# hp6060b_v1_8_add_buffer.net
KiCad netlist of a schematic drawn in EAGLE
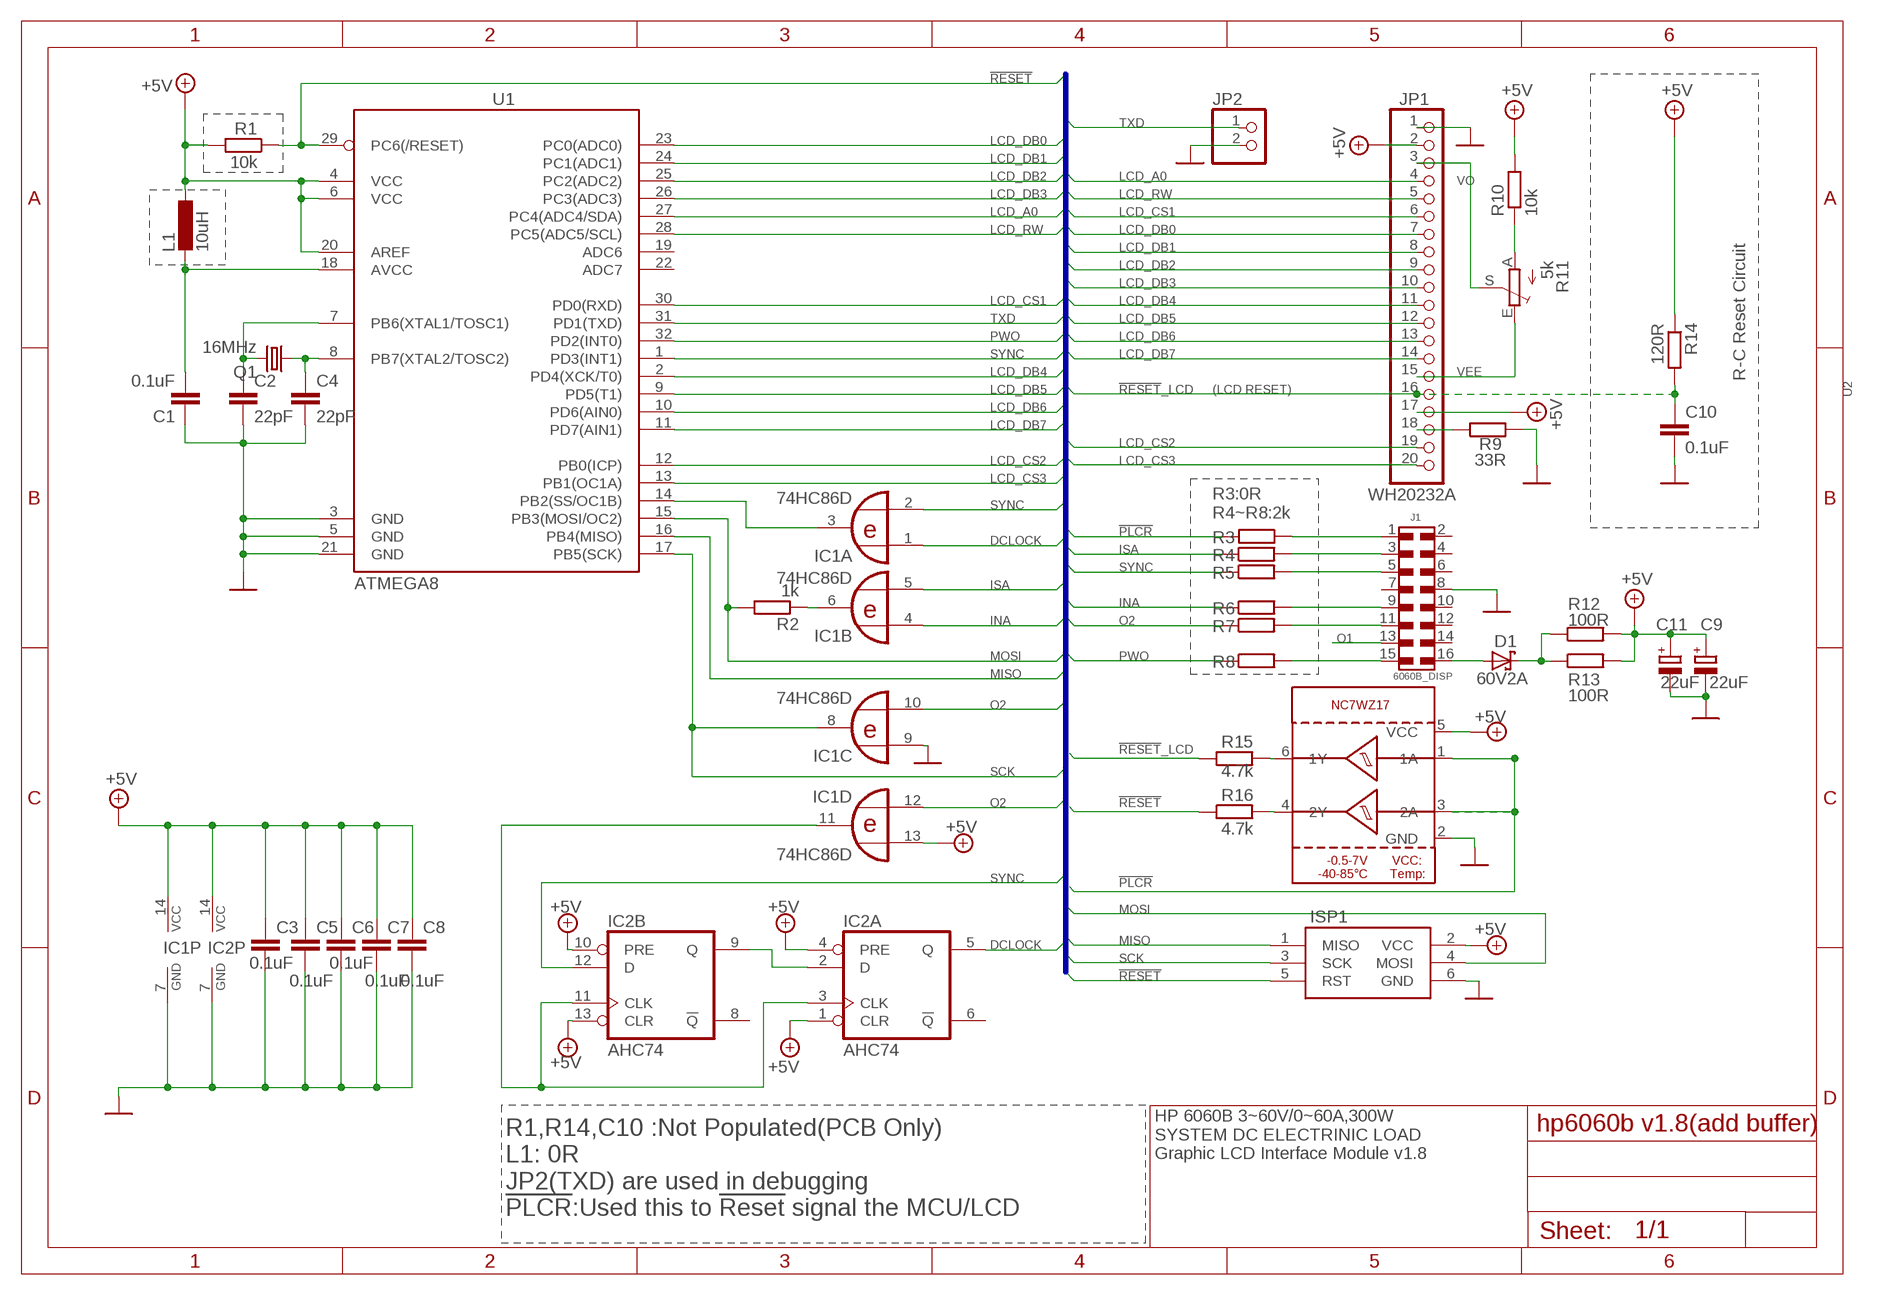
[diagram p0: schematic, sheet 1]

(export (version "E")
  (design (tool "Eeschema 10.0.6"))
  (components
    (comp (ref "C1")
      (value "0.1uF")
      (footprint "eagle-import:C1206")
      (libsource (lib "eagle-import") (part "C-EUC1206"))
    )
    (comp (ref "C2")
      (value "22pF")
      (footprint "eagle-import:C0603")
      (libsource (lib "eagle-import") (part "rcl_334_C-EUC0603"))
    )
    (comp (ref "C3")
      (value "0.1uF")
      (footprint "eagle-import:C1206")
      (libsource (lib "eagle-import") (part "rcl_334_C-EUC1206"))
    )
    (comp (ref "C4")
      (value "22pF")
      (footprint "eagle-import:C0603")
      (libsource (lib "eagle-import") (part "rcl_334_C-EUC0603"))
    )
    (comp (ref "C5")
      (value "0.1uF")
      (footprint "eagle-import:C1206")
      (libsource (lib "eagle-import") (part "rcl_334_C-EUC1206"))
    )
    (comp (ref "C6")
      (value "0.1uF")
      (footprint "eagle-import:C0805")
      (libsource (lib "eagle-import") (part "rcl_334_C-EUC0805"))
    )
    (comp (ref "C7")
      (value "0.1uF")
      (footprint "eagle-import:C0805")
      (libsource (lib "eagle-import") (part "rcl_334_C-EUC0805"))
    )
    (comp (ref "C8")
      (value "0.1uF")
      (footprint "eagle-import:C0805")
      (libsource (lib "eagle-import") (part "rcl_334_C-EUC0805"))
    )
    (comp (ref "C9")
      (value "22uF")
      (footprint "eagle-import:CT7343")
      (libsource (lib "eagle-import") (part "CPOL-EUCT7343"))
    )
    (comp (ref "C10")
      (value "0.1uF")
      (footprint "eagle-import:C0805")
      (libsource (lib "eagle-import") (part "rcl_334_C-EUC0805"))
    )
    (comp (ref "C11")
      (value "22uF")
      (footprint "eagle-import:CT7343")
      (libsource (lib "eagle-import") (part "CPOL-EUCT7343"))
    )
    (comp (ref "D1")
      (value "60V2A")
      (footprint "eagle-import:DIODE_SMB")
      (libsource (lib "eagle-import") (part "SCHOTTKY-DIODE"))
    )
    (comp (ref "IC1")
      (value "74HC86D")
      (footprint "eagle-import:SO14")
      (libsource (lib "eagle-import") (part "7486DHC"))
    )
    (comp (ref "IC2")
      (value "AHC74")
      (footprint "eagle-import:TSSOP-14")
      (libsource (lib "eagle-import") (part "IC_HC74"))
    )
    (comp (ref "ISP1")
      (value "AVRISP-6")
      (footprint "eagle-import:AVRISP")
      (libsource (lib "eagle-import") (part "AVRISP-6"))
    )
    (comp (ref "J1")
      (value "6060B_DISP")
      (footprint "eagle-import:61001621121")
      (libsource (lib "eagle-import") (part "6100XX21121_61001621121"))
    )
    (comp (ref "JP1")
      (value "WH20232A")
      (footprint "eagle-import:1X20_ROUND")
      (libsource (lib "eagle-import") (part "HEADER-1X20ROUND"))
    )
    (comp (ref "JP2")
      (value "HEADER-1X2ROUND")
      (footprint "eagle-import:1X02_ROUND")
      (libsource (lib "eagle-import") (part "HEADER-1X2ROUND"))
    )
    (comp (ref "L1")
      (value "10uH")
      (footprint "eagle-import:L3225M")
      (libsource (lib "eagle-import") (part "L-EUL3225M"))
    )
    (comp (ref "Q1")
      (value "16MHz")
      (footprint "eagle-import:CSM-7X-DU")
      (libsource (lib "eagle-import") (part "CSM-7X-DU"))
    )
    (comp (ref "R1")
      (value "10k")
      (footprint "eagle-import:R1206")
      (libsource (lib "eagle-import") (part "R-EU_R1206"))
    )
    (comp (ref "R2")
      (value "1k")
      (footprint "eagle-import:R1206")
      (libsource (lib "eagle-import") (part "R-EU_R1206"))
    )
    (comp (ref "R3")
      (value "0R")
      (footprint "eagle-import:R1206")
      (libsource (lib "eagle-import") (part "R-EU_R1206"))
    )
    (comp (ref "R4")
      (value "2k")
      (footprint "eagle-import:R1206")
      (libsource (lib "eagle-import") (part "R-EU_R1206"))
    )
    (comp (ref "R5")
      (value "2k")
      (footprint "eagle-import:R1206")
      (libsource (lib "eagle-import") (part "R-EU_R1206"))
    )
    (comp (ref "R6")
      (value "2k")
      (footprint "eagle-import:R1206")
      (libsource (lib "eagle-import") (part "R-EU_R1206"))
    )
    (comp (ref "R7")
      (value "2k")
      (footprint "eagle-import:R1206")
      (libsource (lib "eagle-import") (part "R-EU_R1206"))
    )
    (comp (ref "R8")
      (value "2k")
      (footprint "eagle-import:R1206")
      (libsource (lib "eagle-import") (part "R-EU_R1206"))
    )
    (comp (ref "R9")
      (value "33R")
      (footprint "eagle-import:R2010")
      (libsource (lib "eagle-import") (part "R-EU_R2010"))
    )
    (comp (ref "R10")
      (value "10k")
      (footprint "eagle-import:R1206")
      (libsource (lib "eagle-import") (part "R-EU_R1206"))
    )
    (comp (ref "R11")
      (value "5k")
      (footprint "eagle-import:B25P")
      (libsource (lib "eagle-import") (part "TRIM_EU-B25P"))
    )
    (comp (ref "R12")
      (value "100R")
      (footprint "eagle-import:R1206")
      (libsource (lib "eagle-import") (part "R-EU_R1206"))
    )
    (comp (ref "R13")
      (value "100R")
      (footprint "eagle-import:R1206")
      (libsource (lib "eagle-import") (part "R-EU_R1206"))
    )
    (comp (ref "R14")
      (value "120R")
      (footprint "eagle-import:R0805")
      (libsource (lib "eagle-import") (part "R-EU_R0805"))
    )
    (comp (ref "R15")
      (value "4.7k")
      (footprint "eagle-import:R0805")
      (libsource (lib "eagle-import") (part "R-EU_R0805"))
    )
    (comp (ref "R16")
      (value "4.7k")
      (footprint "eagle-import:R0805")
      (libsource (lib "eagle-import") (part "R-EU_R0805"))
    )
    (comp (ref "U1")
      (value "ATMEGA8")
      (footprint "eagle-import:LQFP32")
      (libsource (lib "eagle-import") (part "IC_ATMEGA8"))
    )
    (comp (ref "U2")
      (value "IC_BUFFER_NC7WZ17P6X")
      (footprint "eagle-import:SOT65P210X110-6N")
      (libsource (lib "eagle-import") (part "IC_BUFFER_NC7WZ17P6X"))
    )
  )
  (nets
    (net (code "1") (name "+5V") (class "Default")
      (node (ref "C11") (pin "+") (pinfunction "+_+") (pintype "passive"))
      (node (ref "C3") (pin "1") (pinfunction "1_1") (pintype "passive"))
      (node (ref "C5") (pin "1") (pinfunction "1_1") (pintype "passive"))
      (node (ref "C6") (pin "1") (pinfunction "1_1") (pintype "passive"))
      (node (ref "C7") (pin "1") (pinfunction "1_1") (pintype "passive"))
      (node (ref "C8") (pin "1") (pinfunction "1_1") (pintype "passive"))
      (node (ref "C9") (pin "+") (pinfunction "+_+") (pintype "passive"))
      (node (ref "IC1") (pin "13") (pinfunction "I1_13") (pintype "input"))
      (node (ref "IC1") (pin "14") (pinfunction "VCC_14") (pintype "power_in"))
      (node (ref "IC2") (pin "1") (pinfunction "CLR_1") (pintype "input"))
      (node (ref "IC2") (pin "10") (pinfunction "PRE_10") (pintype "input"))
      (node (ref "IC2") (pin "13") (pinfunction "CLR_13") (pintype "input"))
      (node (ref "IC2") (pin "14") (pinfunction "VCC_14") (pintype "power_in"))
      (node (ref "IC2") (pin "4") (pinfunction "PRE_4") (pintype "input"))
      (node (ref "ISP1") (pin "2") (pinfunction "VCC_2") (pintype "power_in"))
      (node (ref "JP1") (pin "17") (pinfunction "17_17") (pintype "passive"))
      (node (ref "JP1") (pin "2") (pinfunction "2_2") (pintype "passive"))
      (node (ref "L1") (pin "1") (pinfunction "1_1") (pintype "passive"))
      (node (ref "R1") (pin "2") (pinfunction "2_2") (pintype "passive"))
      (node (ref "R10") (pin "2") (pinfunction "2_2") (pintype "passive"))
      (node (ref "R12") (pin "2") (pinfunction "2_2") (pintype "passive"))
      (node (ref "R13") (pin "2") (pinfunction "2_2") (pintype "passive"))
      (node (ref "R14") (pin "1") (pinfunction "1_1") (pintype "passive"))
      (node (ref "U1") (pin "20") (pinfunction "AREF_20") (pintype "passive"))
      (node (ref "U1") (pin "4") (pinfunction "VCC_4") (pintype "power_in"))
      (node (ref "U1") (pin "6") (pinfunction "VCC_6") (pintype "power_in"))
      (node (ref "U2") (pin "5") (pinfunction "VCC_5") (pintype "power_in"))
    )
    (net (code "2") (name "/DCLOCK") (class "Default")
      (node (ref "IC1") (pin "1") (pinfunction "I0_1") (pintype "input"))
      (node (ref "IC2") (pin "5") (pinfunction "Q_5") (pintype "output"))
    )
    (net (code "3") (name "/INA") (class "Default")
      (node (ref "IC1") (pin "4") (pinfunction "I0_4") (pintype "input"))
      (node (ref "R6") (pin "1") (pinfunction "1_1") (pintype "passive"))
    )
    (net (code "4") (name "/ISA") (class "Default")
      (node (ref "IC1") (pin "5") (pinfunction "I1_5") (pintype "input"))
      (node (ref "R4") (pin "1") (pinfunction "1_1") (pintype "passive"))
    )
    (net (code "5") (name "/LCD_A0") (class "Default")
      (node (ref "JP1") (pin "4") (pinfunction "4_4") (pintype "passive"))
      (node (ref "U1") (pin "27") (pinfunction "PC4(ADC4/SDA)_27") (pintype "bidirectional"))
    )
    (net (code "6") (name "/LCD_CS1") (class "Default")
      (node (ref "JP1") (pin "6") (pinfunction "6_6") (pintype "passive"))
      (node (ref "U1") (pin "30") (pinfunction "PD0(RXD)_30") (pintype "bidirectional"))
    )
    (net (code "7") (name "/LCD_CS2") (class "Default")
      (node (ref "JP1") (pin "19") (pinfunction "19_19") (pintype "passive"))
      (node (ref "U1") (pin "12") (pinfunction "PB0(ICP)_12") (pintype "bidirectional"))
    )
    (net (code "8") (name "/LCD_CS3") (class "Default")
      (node (ref "JP1") (pin "20") (pinfunction "20_20") (pintype "passive"))
      (node (ref "U1") (pin "13") (pinfunction "PB1(OC1A)_13") (pintype "bidirectional"))
    )
    (net (code "9") (name "/LCD_DB0") (class "Default")
      (node (ref "JP1") (pin "7") (pinfunction "7_7") (pintype "passive"))
      (node (ref "U1") (pin "23") (pinfunction "PC0(ADC0)_23") (pintype "bidirectional"))
    )
    (net (code "10") (name "/LCD_DB1") (class "Default")
      (node (ref "JP1") (pin "8") (pinfunction "8_8") (pintype "passive"))
      (node (ref "U1") (pin "24") (pinfunction "PC1(ADC1)_24") (pintype "bidirectional"))
    )
    (net (code "11") (name "/LCD_DB2") (class "Default")
      (node (ref "JP1") (pin "9") (pinfunction "9_9") (pintype "passive"))
      (node (ref "U1") (pin "25") (pinfunction "PC2(ADC2)_25") (pintype "bidirectional"))
    )
    (net (code "12") (name "/LCD_DB3") (class "Default")
      (node (ref "JP1") (pin "10") (pinfunction "10_10") (pintype "passive"))
      (node (ref "U1") (pin "26") (pinfunction "PC3(ADC3)_26") (pintype "bidirectional"))
    )
    (net (code "13") (name "/LCD_DB4") (class "Default")
      (node (ref "JP1") (pin "11") (pinfunction "11_11") (pintype "passive"))
      (node (ref "U1") (pin "2") (pinfunction "PD4(XCK/T0)_2") (pintype "bidirectional"))
    )
    (net (code "14") (name "/LCD_DB5") (class "Default")
      (node (ref "JP1") (pin "12") (pinfunction "12_12") (pintype "passive"))
      (node (ref "U1") (pin "9") (pinfunction "PD5(T1)_9") (pintype "bidirectional"))
    )
    (net (code "15") (name "/LCD_DB6") (class "Default")
      (node (ref "JP1") (pin "13") (pinfunction "13_13") (pintype "passive"))
      (node (ref "U1") (pin "10") (pinfunction "PD6(AIN0)_10") (pintype "bidirectional"))
    )
    (net (code "16") (name "/LCD_DB7") (class "Default")
      (node (ref "JP1") (pin "14") (pinfunction "14_14") (pintype "passive"))
      (node (ref "U1") (pin "11") (pinfunction "PD7(AIN1)_11") (pintype "bidirectional"))
    )
    (net (code "17") (name "/LCD_RW") (class "Default")
      (node (ref "JP1") (pin "5") (pinfunction "5_5") (pintype "passive"))
      (node (ref "U1") (pin "28") (pinfunction "PC5(ADC5/SCL)_28") (pintype "bidirectional"))
    )
    (net (code "18") (name "/MISO") (class "Default")
      (node (ref "ISP1") (pin "1") (pinfunction "MISO_1") (pintype "input"))
      (node (ref "U1") (pin "16") (pinfunction "PB4(MISO)_16") (pintype "bidirectional"))
    )
    (net (code "19") (name "/MOSI") (class "Default")
      (node (ref "ISP1") (pin "4") (pinfunction "MOSI_4") (pintype "output"))
      (node (ref "R2") (pin "2") (pinfunction "2_2") (pintype "passive"))
      (node (ref "U1") (pin "15") (pinfunction "PB3(MOSI/OC2)_15") (pintype "bidirectional"))
    )
    (net (code "20") (name "/O1") (class "Default")
      (node (ref "J1") (pin "13") (pinfunction "13_13") (pintype "passive"))
    )
    (net (code "21") (name "/O2") (class "Default")
      (node (ref "IC1") (pin "10") (pinfunction "I1_10") (pintype "input"))
      (node (ref "IC1") (pin "12") (pinfunction "I0_12") (pintype "input"))
      (node (ref "R7") (pin "1") (pinfunction "1_1") (pintype "passive"))
    )
    (net (code "22") (name "/PWO") (class "Default")
      (node (ref "R8") (pin "1") (pinfunction "1_1") (pintype "passive"))
      (node (ref "U1") (pin "32") (pinfunction "PD2(INT0)_32") (pintype "bidirectional"))
    )
    (net (code "23") (name "/SCK") (class "Default")
      (node (ref "IC1") (pin "8") (pinfunction "O_8") (pintype "output"))
      (node (ref "ISP1") (pin "3") (pinfunction "SCK_3") (pintype "output"))
      (node (ref "U1") (pin "17") (pinfunction "PB5(SCK)_17") (pintype "bidirectional"))
    )
    (net (code "24") (name "/SYNC") (class "Default")
      (node (ref "IC1") (pin "2") (pinfunction "I1_2") (pintype "input"))
      (node (ref "IC2") (pin "12") (pinfunction "D_12") (pintype "input"))
      (node (ref "R5") (pin "1") (pinfunction "1_1") (pintype "passive"))
      (node (ref "U1") (pin "1") (pinfunction "PD3(INT1)_1") (pintype "bidirectional"))
    )
    (net (code "25") (name "/TXD") (class "Default")
      (node (ref "JP2") (pin "1") (pinfunction "1_1") (pintype "passive"))
      (node (ref "U1") (pin "31") (pinfunction "PD1(TXD)_31") (pintype "bidirectional"))
    )
    (net (code "26") (name "/VEE") (class "Default")
      (node (ref "JP1") (pin "15") (pinfunction "15_15") (pintype "passive"))
      (node (ref "R11") (pin "E") (pinfunction "E_E") (pintype "passive"))
    )
    (net (code "27") (name "/VO") (class "Default")
      (node (ref "JP1") (pin "3") (pinfunction "3_3") (pintype "passive"))
      (node (ref "R11") (pin "S") (pinfunction "S_S") (pintype "passive"))
    )
    (net (code "28") (name "/~{PLCR}") (class "Default")
      (node (ref "R3") (pin "2") (pinfunction "2_2") (pintype "passive"))
      (node (ref "U2") (pin "1") (pinfunction "1A_1") (pintype "input"))
      (node (ref "U2") (pin "3") (pinfunction "2A_3") (pintype "input"))
    )
    (net (code "29") (name "/~{RESET}") (class "Default")
      (node (ref "ISP1") (pin "5") (pinfunction "RST_5") (pintype "output"))
      (node (ref "R1") (pin "1") (pinfunction "1_1") (pintype "passive"))
      (node (ref "R16") (pin "1") (pinfunction "1_1") (pintype "passive"))
      (node (ref "U1") (pin "29") (pinfunction "PC6(/RESET)_29") (pintype "bidirectional"))
    )
    (net (code "30") (name "/~{RESET}_LCD") (class "Default")
      (node (ref "C10") (pin "1") (pinfunction "1_1") (pintype "passive"))
      (node (ref "JP1") (pin "16") (pinfunction "16_16") (pintype "passive"))
      (node (ref "R14") (pin "2") (pinfunction "2_2") (pintype "passive"))
      (node (ref "R15") (pin "1") (pinfunction "1_1") (pintype "passive"))
    )
    (net (code "31") (name "GND") (class "Default")
      (node (ref "C1") (pin "1") (pinfunction "1_1") (pintype "passive"))
      (node (ref "C10") (pin "2") (pinfunction "2_2") (pintype "passive"))
      (node (ref "C11") (pin "-") (pinfunction "-_-") (pintype "passive"))
      (node (ref "C2") (pin "2") (pinfunction "2_2") (pintype "passive"))
      (node (ref "C3") (pin "2") (pinfunction "2_2") (pintype "passive"))
      (node (ref "C4") (pin "2") (pinfunction "2_2") (pintype "passive"))
      (node (ref "C5") (pin "2") (pinfunction "2_2") (pintype "passive"))
      (node (ref "C6") (pin "2") (pinfunction "2_2") (pintype "passive"))
      (node (ref "C7") (pin "2") (pinfunction "2_2") (pintype "passive"))
      (node (ref "C8") (pin "2") (pinfunction "2_2") (pintype "passive"))
      (node (ref "C9") (pin "-") (pinfunction "-_-") (pintype "passive"))
      (node (ref "IC1") (pin "7") (pinfunction "GND_7") (pintype "power_in"))
      (node (ref "IC1") (pin "9") (pinfunction "I0_9") (pintype "input"))
      (node (ref "IC2") (pin "7") (pinfunction "GND_7") (pintype "power_in"))
      (node (ref "ISP1") (pin "6") (pinfunction "GND_6") (pintype "power_in"))
      (node (ref "J1") (pin "8") (pinfunction "8_8") (pintype "passive"))
      (node (ref "JP1") (pin "1") (pinfunction "1_1") (pintype "passive"))
      (node (ref "JP2") (pin "2") (pinfunction "2_2") (pintype "passive"))
      (node (ref "R9") (pin "2") (pinfunction "2_2") (pintype "passive"))
      (node (ref "U1") (pin "21") (pinfunction "GND_21") (pintype "power_in"))
      (node (ref "U1") (pin "3") (pinfunction "GND_3") (pintype "power_in"))
      (node (ref "U1") (pin "5") (pinfunction "GND_5") (pintype "power_in"))
      (node (ref "U2") (pin "2") (pinfunction "GND_2") (pintype "power_in"))
    )
    (net (code "32") (name "Net-(D1-A)") (class "Default")
      (node (ref "D1") (pin "C") (pinfunction "A_C") (pintype "passive"))
      (node (ref "R12") (pin "1") (pinfunction "1_1") (pintype "passive"))
      (node (ref "R13") (pin "1") (pinfunction "1_1") (pintype "passive"))
    )
    (net (code "33") (name "Net-(D1-C)") (class "Default")
      (node (ref "D1") (pin "A") (pinfunction "C_A") (pintype "passive"))
      (node (ref "J1") (pin "16") (pinfunction "16_16") (pintype "passive"))
    )
    (net (code "34") (name "Net-(IC1A-O)") (class "Default")
      (node (ref "IC1") (pin "3") (pinfunction "O_3") (pintype "output"))
      (node (ref "U1") (pin "14") (pinfunction "PB2(SS/OC1B)_14") (pintype "bidirectional"))
    )
    (net (code "35") (name "Net-(IC1B-O)") (class "Default")
      (node (ref "IC1") (pin "6") (pinfunction "O_6") (pintype "output"))
      (node (ref "R2") (pin "1") (pinfunction "1_1") (pintype "passive"))
    )
    (net (code "36") (name "Net-(IC1D-O)") (class "Default")
      (node (ref "IC1") (pin "11") (pinfunction "O_11") (pintype "output"))
      (node (ref "IC2") (pin "11") (pinfunction "CLK_11") (pintype "input"))
      (node (ref "IC2") (pin "3") (pinfunction "CLK_3") (pintype "input"))
    )
    (net (code "37") (name "Net-(IC2A-D)") (class "Default")
      (node (ref "IC2") (pin "2") (pinfunction "D_2") (pintype "input"))
      (node (ref "IC2") (pin "9") (pinfunction "Q_9") (pintype "output"))
    )
    (net (code "38") (name "Net-(J1-Pad1)") (class "Default")
      (node (ref "J1") (pin "1") (pinfunction "1_1") (pintype "passive"))
      (node (ref "R3") (pin "1") (pinfunction "1_1") (pintype "passive"))
    )
    (net (code "39") (name "Net-(J1-Pad3)") (class "Default")
      (node (ref "J1") (pin "3") (pinfunction "3_3") (pintype "passive"))
      (node (ref "R4") (pin "2") (pinfunction "2_2") (pintype "passive"))
    )
    (net (code "40") (name "Net-(J1-Pad5)") (class "Default")
      (node (ref "J1") (pin "5") (pinfunction "5_5") (pintype "passive"))
      (node (ref "R5") (pin "2") (pinfunction "2_2") (pintype "passive"))
    )
    (net (code "41") (name "Net-(J1-Pad9)") (class "Default")
      (node (ref "J1") (pin "9") (pinfunction "9_9") (pintype "passive"))
      (node (ref "R6") (pin "2") (pinfunction "2_2") (pintype "passive"))
    )
    (net (code "42") (name "Net-(J1-Pad11)") (class "Default")
      (node (ref "J1") (pin "11") (pinfunction "11_11") (pintype "passive"))
      (node (ref "R7") (pin "2") (pinfunction "2_2") (pintype "passive"))
    )
    (net (code "43") (name "Net-(J1-Pad15)") (class "Default")
      (node (ref "J1") (pin "15") (pinfunction "15_15") (pintype "passive"))
      (node (ref "R8") (pin "2") (pinfunction "2_2") (pintype "passive"))
    )
    (net (code "44") (name "Net-(JP1-Pad18)") (class "Default")
      (node (ref "JP1") (pin "18") (pinfunction "18_18") (pintype "passive"))
      (node (ref "R9") (pin "1") (pinfunction "1_1") (pintype "passive"))
    )
    (net (code "45") (name "Net-(R10-Pad1)") (class "Default")
      (node (ref "R10") (pin "1") (pinfunction "1_1") (pintype "passive"))
      (node (ref "R11") (pin "A") (pinfunction "A_A") (pintype "passive"))
    )
    (net (code "46") (name "Net-(U1-AVCC)") (class "Default")
      (node (ref "C1") (pin "2") (pinfunction "2_2") (pintype "passive"))
      (node (ref "L1") (pin "2") (pinfunction "2_2") (pintype "passive"))
      (node (ref "U1") (pin "18") (pinfunction "AVCC_18") (pintype "power_in"))
    )
    (net (code "47") (name "Net-(U1-PB6(XTAL1{slash}TOSC1))") (class "Default")
      (node (ref "C2") (pin "1") (pinfunction "1_1") (pintype "passive"))
      (node (ref "Q1") (pin "2") (pinfunction "2_2") (pintype "passive"))
      (node (ref "U1") (pin "7") (pinfunction "PB6(XTAL1/TOSC1)_7") (pintype "bidirectional"))
    )
    (net (code "48") (name "Net-(U1-PB7(XTAL2{slash}TOSC2))") (class "Default")
      (node (ref "C4") (pin "1") (pinfunction "1_1") (pintype "passive"))
      (node (ref "Q1") (pin "1") (pinfunction "1_1") (pintype "passive"))
      (node (ref "U1") (pin "8") (pinfunction "PB7(XTAL2/TOSC2)_8") (pintype "bidirectional"))
    )
    (net (code "49") (name "Net-(U2-1Y)") (class "Default")
      (node (ref "R15") (pin "2") (pinfunction "2_2") (pintype "passive"))
      (node (ref "U2") (pin "6") (pinfunction "1Y_6") (pintype "output"))
    )
    (net (code "50") (name "Net-(U2-2Y)") (class "Default")
      (node (ref "R16") (pin "2") (pinfunction "2_2") (pintype "passive"))
      (node (ref "U2") (pin "4") (pinfunction "2Y_4") (pintype "output"))
    )
    (net (code "51") (name "unconnected-(IC2A-~{Q}-Pad6)") (class "Default")
      (node (ref "IC2") (pin "6") (pinfunction "~{Q}_6") (pintype "output"))
    )
    (net (code "52") (name "unconnected-(IC2B-~{Q}-Pad8)") (class "Default")
      (node (ref "IC2") (pin "8") (pinfunction "~{Q}_8") (pintype "output"))
    )
    (net (code "53") (name "unconnected-(J1-Pad2)") (class "Default")
      (node (ref "J1") (pin "2") (pinfunction "2_2") (pintype "passive"))
    )
    (net (code "54") (name "unconnected-(J1-Pad4)") (class "Default")
      (node (ref "J1") (pin "4") (pinfunction "4_4") (pintype "passive"))
    )
    (net (code "55") (name "unconnected-(J1-Pad6)") (class "Default")
      (node (ref "J1") (pin "6") (pinfunction "6_6") (pintype "passive"))
    )
    (net (code "56") (name "unconnected-(J1-Pad7)") (class "Default")
      (node (ref "J1") (pin "7") (pinfunction "7_7") (pintype "passive"))
    )
    (net (code "57") (name "unconnected-(J1-Pad10)") (class "Default")
      (node (ref "J1") (pin "10") (pinfunction "10_10") (pintype "passive"))
    )
    (net (code "58") (name "unconnected-(J1-Pad12)") (class "Default")
      (node (ref "J1") (pin "12") (pinfunction "12_12") (pintype "passive"))
    )
    (net (code "59") (name "unconnected-(J1-Pad14)") (class "Default")
      (node (ref "J1") (pin "14") (pinfunction "14_14") (pintype "passive"))
    )
    (net (code "60") (name "unconnected-(U1-ADC6-Pad19)") (class "Default")
      (node (ref "U1") (pin "19") (pinfunction "ADC6_19") (pintype "bidirectional"))
    )
    (net (code "61") (name "unconnected-(U1-ADC7-Pad22)") (class "Default")
      (node (ref "U1") (pin "22") (pinfunction "ADC7_22") (pintype "bidirectional"))
    )
  )
)
